# C64_KernalSw_16k.net
KiCad netlist of a schematic drawn in EAGLE
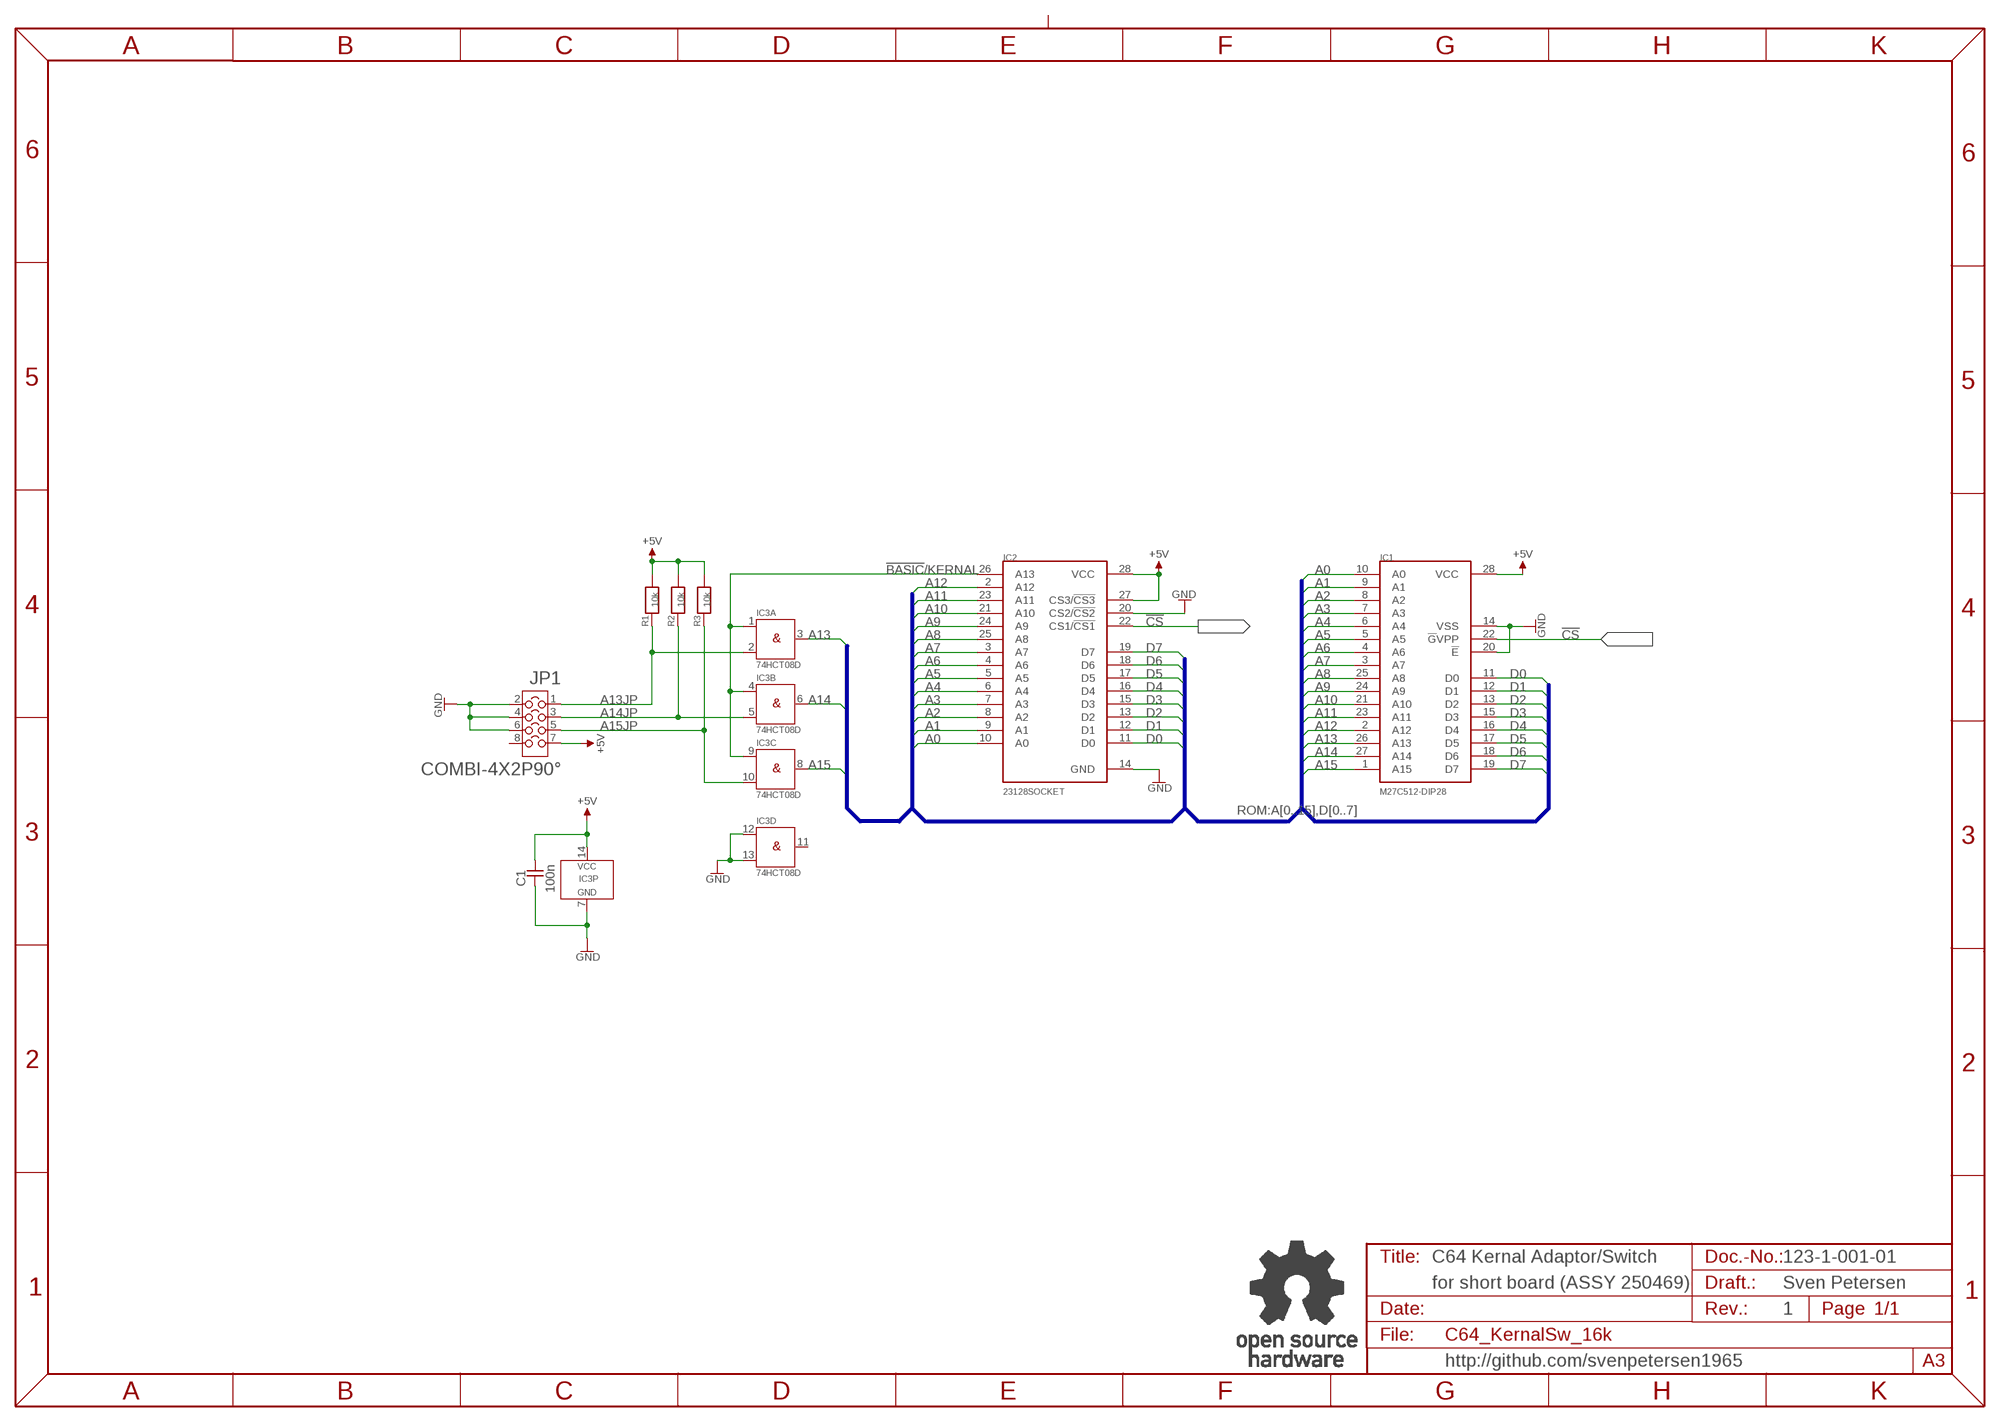
[diagram p0: schematic, sheet 1]

(export (version "E")
  (design (tool "Eeschema 10.0.6"))
  (components
    (comp (ref "C1")
      (value "100n")
      (footprint "eagle-import:0805")
      (libsource (lib "eagle-import") (part "C-0805"))
    )
    (comp (ref "IC1")
      (value "M27C512-DIP28")
      (footprint "eagle-import:DIL28-6")
      (libsource (lib "eagle-import") (part "M27C512-DIP28"))
    )
    (comp (ref "IC2")
      (value "23128SOCKET")
      (footprint "eagle-import:DIL28_SOCKET")
      (libsource (lib "eagle-import") (part "23128SOCKET"))
    )
    (comp (ref "IC3")
      (value "74HCT08D")
      (footprint "eagle-import:SO-14")
      (libsource (lib "eagle-import") (part "7408HC"))
    )
    (comp (ref "JP1")
      (value "COMBI-4X2P90°")
      (footprint "eagle-import:COMBI-4X2-90")
      (libsource (lib "eagle-import") (part "COMBI-4X2P90°"))
    )
    (comp (ref "R1")
      (value "10k")
      (footprint "eagle-import:0805")
      (libsource (lib "eagle-import") (part "R-0805"))
    )
    (comp (ref "R2")
      (value "10k")
      (footprint "eagle-import:0805")
      (libsource (lib "eagle-import") (part "R-0805"))
    )
    (comp (ref "R3")
      (value "10k")
      (footprint "eagle-import:0805")
      (libsource (lib "eagle-import") (part "R-0805"))
    )
    (comp (ref "U$21")
      (value "OPEN_SOURCE_HW")
      (footprint "eagle-import:OPENHW")
      (libsource (lib "eagle-import") (part "OPEN_SOURCE_HW"))
    )
  )
  (nets
    (net (code "1") (name "+5V") (class "Default")
      (node (ref "C1") (pin "2") (pinfunction "2_2") (pintype "passive"))
      (node (ref "IC1") (pin "28") (pinfunction "VCC_28") (pintype "power_in"))
      (node (ref "IC2") (pin "27") (pinfunction "CS3/~{CS3}_27") (pintype "input"))
      (node (ref "IC2") (pin "28") (pinfunction "VCC_28") (pintype "power_in"))
      (node (ref "IC3") (pin "14") (pinfunction "VCC_14") (pintype "bidirectional"))
      (node (ref "JP1") (pin "7") (pinfunction "7_7") (pintype "bidirectional"))
      (node (ref "R1") (pin "2") (pinfunction "2_2") (pintype "passive"))
      (node (ref "R2") (pin "2") (pinfunction "2_2") (pintype "passive"))
      (node (ref "R3") (pin "2") (pinfunction "2_2") (pintype "passive"))
    )
    (net (code "2") (name "/A0") (class "Default")
      (node (ref "IC1") (pin "10") (pinfunction "A0_10") (pintype "input"))
      (node (ref "IC2") (pin "10") (pinfunction "A0_10") (pintype "input"))
    )
    (net (code "3") (name "/A1") (class "Default")
      (node (ref "IC1") (pin "9") (pinfunction "A1_9") (pintype "input"))
      (node (ref "IC2") (pin "9") (pinfunction "A1_9") (pintype "input"))
    )
    (net (code "4") (name "/A2") (class "Default")
      (node (ref "IC1") (pin "8") (pinfunction "A2_8") (pintype "input"))
      (node (ref "IC2") (pin "8") (pinfunction "A2_8") (pintype "input"))
    )
    (net (code "5") (name "/A3") (class "Default")
      (node (ref "IC1") (pin "7") (pinfunction "A3_7") (pintype "input"))
      (node (ref "IC2") (pin "7") (pinfunction "A3_7") (pintype "input"))
    )
    (net (code "6") (name "/A4") (class "Default")
      (node (ref "IC1") (pin "6") (pinfunction "A4_6") (pintype "input"))
      (node (ref "IC2") (pin "6") (pinfunction "A4_6") (pintype "input"))
    )
    (net (code "7") (name "/A5") (class "Default")
      (node (ref "IC1") (pin "5") (pinfunction "A5_5") (pintype "input"))
      (node (ref "IC2") (pin "5") (pinfunction "A5_5") (pintype "input"))
    )
    (net (code "8") (name "/A6") (class "Default")
      (node (ref "IC1") (pin "4") (pinfunction "A6_4") (pintype "input"))
      (node (ref "IC2") (pin "4") (pinfunction "A6_4") (pintype "input"))
    )
    (net (code "9") (name "/A7") (class "Default")
      (node (ref "IC1") (pin "3") (pinfunction "A7_3") (pintype "input"))
      (node (ref "IC2") (pin "3") (pinfunction "A7_3") (pintype "input"))
    )
    (net (code "10") (name "/A8") (class "Default")
      (node (ref "IC1") (pin "25") (pinfunction "A8_25") (pintype "input"))
      (node (ref "IC2") (pin "25") (pinfunction "A8_25") (pintype "input"))
    )
    (net (code "11") (name "/A9") (class "Default")
      (node (ref "IC1") (pin "24") (pinfunction "A9_24") (pintype "input"))
      (node (ref "IC2") (pin "24") (pinfunction "A9_24") (pintype "input"))
    )
    (net (code "12") (name "/A10") (class "Default")
      (node (ref "IC1") (pin "21") (pinfunction "A10_21") (pintype "input"))
      (node (ref "IC2") (pin "21") (pinfunction "A10_21") (pintype "input"))
    )
    (net (code "13") (name "/A11") (class "Default")
      (node (ref "IC1") (pin "23") (pinfunction "A11_23") (pintype "input"))
      (node (ref "IC2") (pin "23") (pinfunction "A11_23") (pintype "input"))
    )
    (net (code "14") (name "/A12") (class "Default")
      (node (ref "IC1") (pin "2") (pinfunction "A12_2") (pintype "input"))
      (node (ref "IC2") (pin "2") (pinfunction "A12_2") (pintype "input"))
    )
    (net (code "15") (name "/A13") (class "Default")
      (node (ref "IC1") (pin "26") (pinfunction "A13_26") (pintype "input"))
      (node (ref "IC3") (pin "3") (pinfunction "O_3") (pintype "output"))
    )
    (net (code "16") (name "/A13JP") (class "Default")
      (node (ref "IC3") (pin "2") (pinfunction "I1_2") (pintype "input"))
      (node (ref "JP1") (pin "1") (pinfunction "1_1") (pintype "bidirectional"))
      (node (ref "R1") (pin "1") (pinfunction "1_1") (pintype "passive"))
    )
    (net (code "17") (name "/A14") (class "Default")
      (node (ref "IC1") (pin "27") (pinfunction "A14_27") (pintype "input"))
      (node (ref "IC3") (pin "6") (pinfunction "O_6") (pintype "output"))
    )
    (net (code "18") (name "/A14JP") (class "Default")
      (node (ref "IC3") (pin "5") (pinfunction "I1_5") (pintype "input"))
      (node (ref "JP1") (pin "3") (pinfunction "3_3") (pintype "bidirectional"))
      (node (ref "R2") (pin "1") (pinfunction "1_1") (pintype "passive"))
    )
    (net (code "19") (name "/A15") (class "Default")
      (node (ref "IC1") (pin "1") (pinfunction "A15_1") (pintype "input"))
      (node (ref "IC3") (pin "8") (pinfunction "O_8") (pintype "output"))
    )
    (net (code "20") (name "/A15JP") (class "Default")
      (node (ref "IC3") (pin "10") (pinfunction "I1_10") (pintype "input"))
      (node (ref "JP1") (pin "5") (pinfunction "5_5") (pintype "bidirectional"))
      (node (ref "R3") (pin "1") (pinfunction "1_1") (pintype "passive"))
    )
    (net (code "21") (name "/D0") (class "Default")
      (node (ref "IC1") (pin "11") (pinfunction "D0_11") (pintype "bidirectional"))
      (node (ref "IC2") (pin "11") (pinfunction "D0_11") (pintype "tri_state"))
    )
    (net (code "22") (name "/D1") (class "Default")
      (node (ref "IC1") (pin "12") (pinfunction "D1_12") (pintype "bidirectional"))
      (node (ref "IC2") (pin "12") (pinfunction "D1_12") (pintype "tri_state"))
    )
    (net (code "23") (name "/D2") (class "Default")
      (node (ref "IC1") (pin "13") (pinfunction "D2_13") (pintype "bidirectional"))
      (node (ref "IC2") (pin "13") (pinfunction "D2_13") (pintype "tri_state"))
    )
    (net (code "24") (name "/D3") (class "Default")
      (node (ref "IC1") (pin "15") (pinfunction "D3_15") (pintype "bidirectional"))
      (node (ref "IC2") (pin "15") (pinfunction "D3_15") (pintype "tri_state"))
    )
    (net (code "25") (name "/D4") (class "Default")
      (node (ref "IC1") (pin "16") (pinfunction "D4_16") (pintype "bidirectional"))
      (node (ref "IC2") (pin "16") (pinfunction "D4_16") (pintype "tri_state"))
    )
    (net (code "26") (name "/D5") (class "Default")
      (node (ref "IC1") (pin "17") (pinfunction "D5_17") (pintype "bidirectional"))
      (node (ref "IC2") (pin "17") (pinfunction "D5_17") (pintype "tri_state"))
    )
    (net (code "27") (name "/D6") (class "Default")
      (node (ref "IC1") (pin "18") (pinfunction "D6_18") (pintype "bidirectional"))
      (node (ref "IC2") (pin "18") (pinfunction "D6_18") (pintype "tri_state"))
    )
    (net (code "28") (name "/D7") (class "Default")
      (node (ref "IC1") (pin "19") (pinfunction "D7_19") (pintype "bidirectional"))
      (node (ref "IC2") (pin "19") (pinfunction "D7_19") (pintype "tri_state"))
    )
    (net (code "30") (name "/~{BASIC}{slash}KERNAL") (class "Default")
      (node (ref "IC2") (pin "26") (pinfunction "A13_26") (pintype "input"))
      (node (ref "IC3") (pin "1") (pinfunction "I0_1") (pintype "input"))
      (node (ref "IC3") (pin "4") (pinfunction "I0_4") (pintype "input"))
      (node (ref "IC3") (pin "9") (pinfunction "I0_9") (pintype "input"))
    )
    (net (code "31") (name "/~{CS}") (class "Default")
      (node (ref "IC1") (pin "22") (pinfunction "~{G}VPP_22") (pintype "input"))
      (node (ref "IC2") (pin "22") (pinfunction "CS1/~{CS1}_22") (pintype "input"))
    )
    (net (code "32") (name "GND") (class "Default")
      (node (ref "C1") (pin "1") (pinfunction "1_1") (pintype "passive"))
      (node (ref "IC1") (pin "14") (pinfunction "VSS_14") (pintype "power_in"))
      (node (ref "IC1") (pin "20") (pinfunction "~{E}_20") (pintype "input"))
      (node (ref "IC2") (pin "14") (pinfunction "GND_14") (pintype "power_in"))
      (node (ref "IC2") (pin "20") (pinfunction "CS2/~{CS2}_20") (pintype "input"))
      (node (ref "IC3") (pin "12") (pinfunction "I0_12") (pintype "input"))
      (node (ref "IC3") (pin "13") (pinfunction "I1_13") (pintype "input"))
      (node (ref "IC3") (pin "7") (pinfunction "GND_7") (pintype "bidirectional"))
      (node (ref "JP1") (pin "2") (pinfunction "2_2") (pintype "bidirectional"))
      (node (ref "JP1") (pin "4") (pinfunction "4_4") (pintype "bidirectional"))
      (node (ref "JP1") (pin "6") (pinfunction "6_6") (pintype "bidirectional"))
    )
    (net (code "33") (name "unconnected-(IC3D-O-Pad11)") (class "Default")
      (node (ref "IC3") (pin "11") (pinfunction "O_11") (pintype "output"))
    )
    (net (code "34") (name "unconnected-(JP1-Pad8)") (class "Default")
      (node (ref "JP1") (pin "8") (pinfunction "8_8") (pintype "bidirectional"))
    )
  )
)
